# IOTBee-v1_1.net
KiCad netlist of a schematic drawn in EAGLE
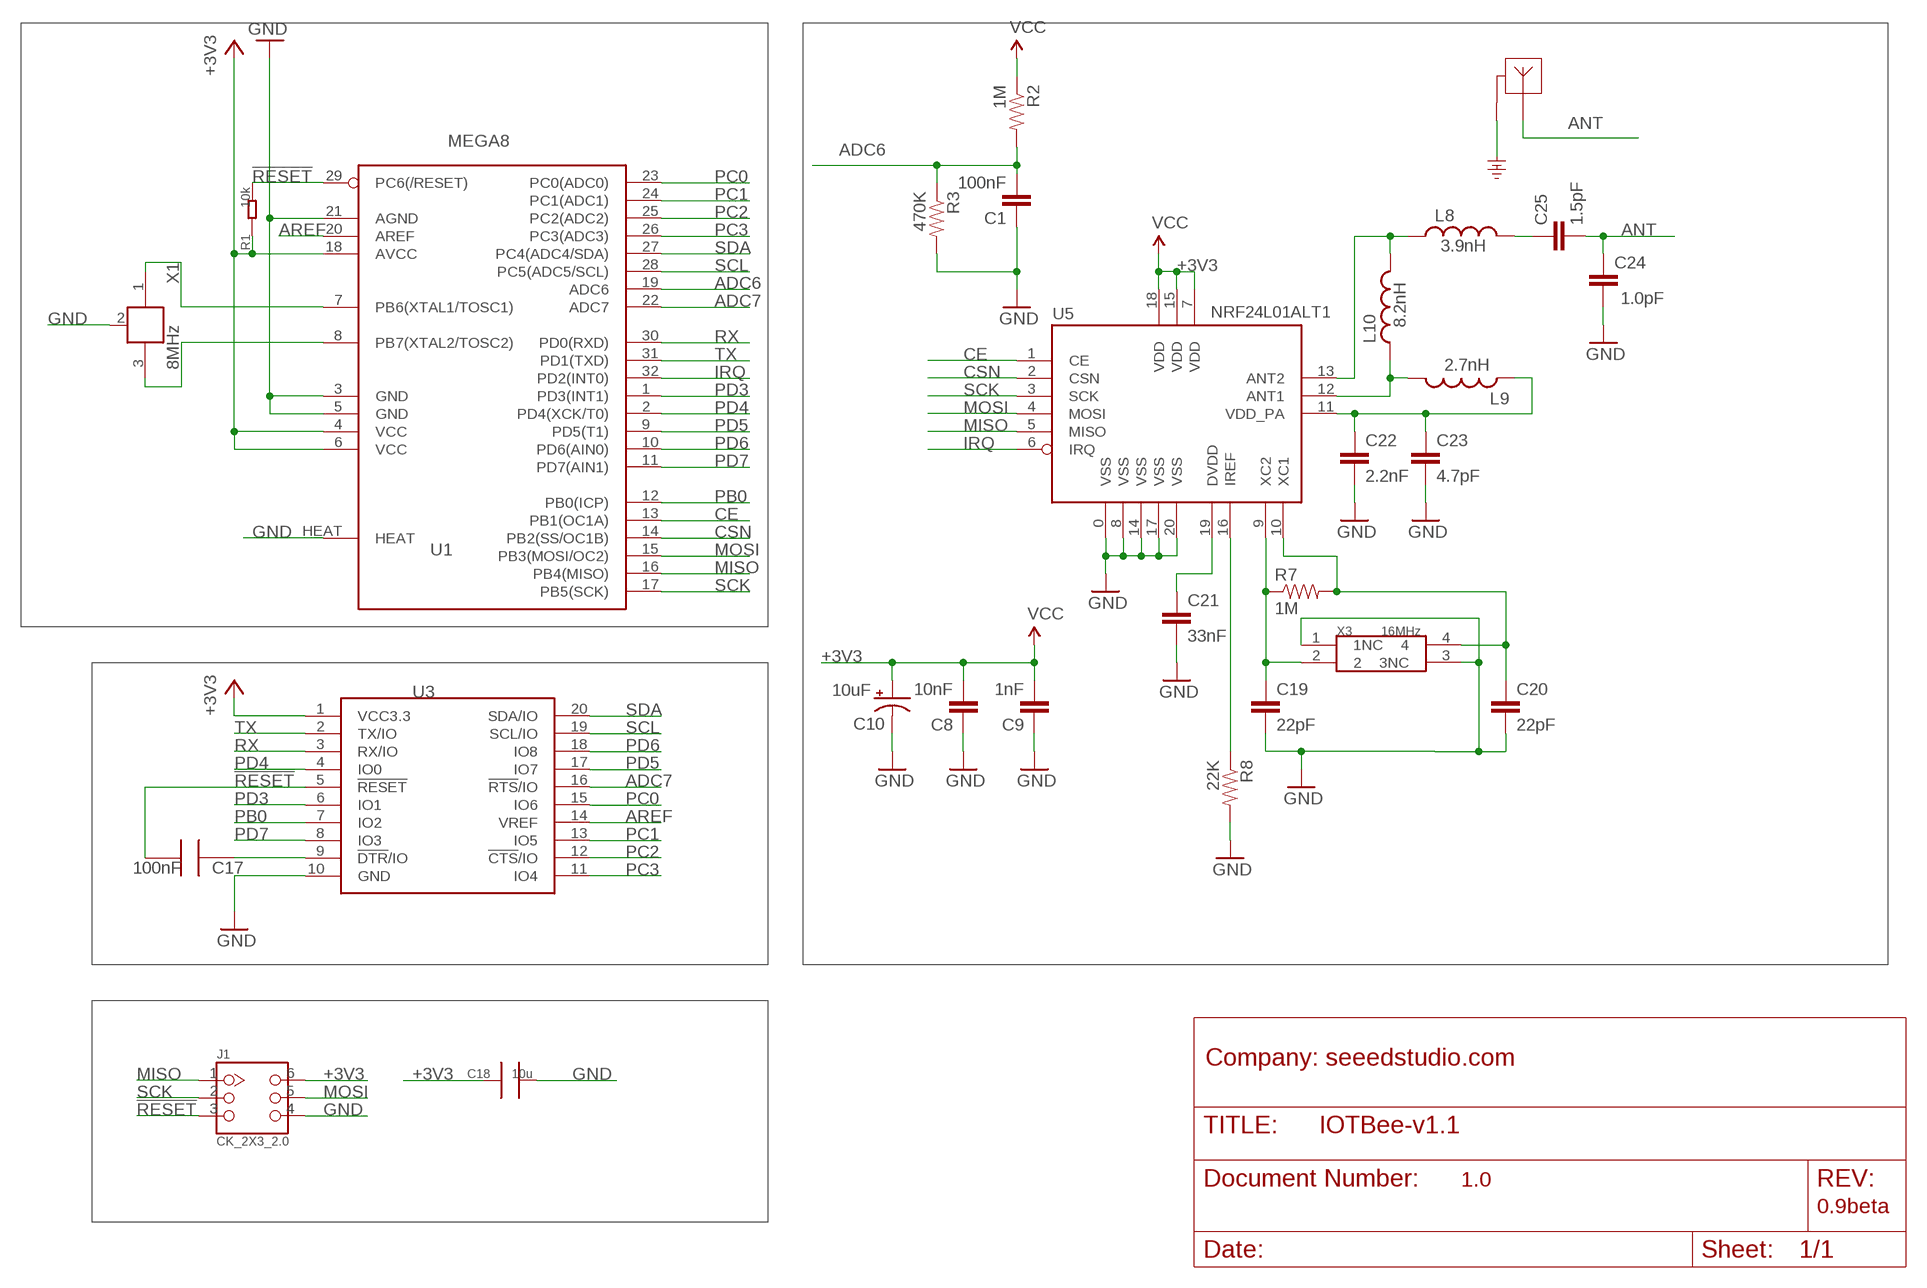
[diagram p0: schematic, sheet 1]

(export (version "E")
  (design (tool "Eeschema 10.0.6"))
  (components
    (comp (ref "ANT1")
      (value "2.4G-ANT")
      (footprint "eagle-import:2.4G-ANT")
      (libsource (lib "eagle-import") (part "2.4G-ANT"))
    )
    (comp (ref "C1")
      (value "100nF")
      (footprint "eagle-import:0402-CAP")
      (libsource (lib "eagle-import") (part "CAP0402-CAP"))
    )
    (comp (ref "C8")
      (value "10nF")
      (footprint "eagle-import:0402-CAP")
      (libsource (lib "eagle-import") (part "CAP0402-CAP"))
    )
    (comp (ref "C9")
      (value "1nF")
      (footprint "eagle-import:0402-CAP")
      (libsource (lib "eagle-import") (part "CAP0402-CAP"))
    )
    (comp (ref "C10")
      (value "10uF")
      (footprint "eagle-import:EIA3528")
      (libsource (lib "eagle-import") (part "CAP_POL3528"))
    )
    (comp (ref "C17")
      (value "100nF")
      (footprint "eagle-import:0603_S")
      (libsource (lib "eagle-import") (part "C0603_S"))
    )
    (comp (ref "C18")
      (value "10u")
      (footprint "eagle-import:0805")
      (libsource (lib "eagle-import") (part "C0805"))
    )
    (comp (ref "C19")
      (value "22pF")
      (footprint "eagle-import:0402-CAP")
      (libsource (lib "eagle-import") (part "CAP0402-CAP"))
    )
    (comp (ref "C20")
      (value "22pF")
      (footprint "eagle-import:0402-CAP")
      (libsource (lib "eagle-import") (part "CAP0402-CAP"))
    )
    (comp (ref "C21")
      (value "33nF")
      (footprint "eagle-import:0402-CAP")
      (libsource (lib "eagle-import") (part "CAP0402-CAP"))
    )
    (comp (ref "C22")
      (value "2.2nF")
      (footprint "eagle-import:0402-CAP")
      (libsource (lib "eagle-import") (part "CAP0402-CAP"))
    )
    (comp (ref "C23")
      (value "4.7pF")
      (footprint "eagle-import:0402-CAP")
      (libsource (lib "eagle-import") (part "CAP0402-CAP"))
    )
    (comp (ref "C24")
      (value "1.0pF")
      (footprint "eagle-import:0402-CAP")
      (libsource (lib "eagle-import") (part "CAP0402-CAP"))
    )
    (comp (ref "C25")
      (value "1.5pF")
      (footprint "eagle-import:0402-CAP")
      (libsource (lib "eagle-import") (part "CAP0402-CAP"))
    )
    (comp (ref "J1")
      (value "CK_2X3_2.0")
      (footprint "eagle-import:CK_2X3_2.0")
      (libsource (lib "eagle-import") (part "CK_2X3_2.0"))
    )
    (comp (ref "L8")
      (value "3.9nH")
      (footprint "eagle-import:C0402")
      (libsource (lib "eagle-import") (part "INDUCTOR0402"))
    )
    (comp (ref "L9")
      (value "2.7nH")
      (footprint "eagle-import:C0402")
      (libsource (lib "eagle-import") (part "INDUCTOR0402"))
    )
    (comp (ref "L10")
      (value "8.2nH")
      (footprint "eagle-import:C0402")
      (libsource (lib "eagle-import") (part "INDUCTOR0402"))
    )
    (comp (ref "R1")
      (value "10k")
      (footprint "eagle-import:0603_S")
      (libsource (lib "eagle-import") (part "R0603_S"))
    )
    (comp (ref "R2")
      (value "1M")
      (footprint "eagle-import:0402-RES")
      (libsource (lib "eagle-import") (part "RESISTOR0402-RES"))
    )
    (comp (ref "R3")
      (value "470K")
      (footprint "eagle-import:0402-RES")
      (libsource (lib "eagle-import") (part "RESISTOR0402-RES"))
    )
    (comp (ref "R7")
      (value "1M")
      (footprint "eagle-import:0402-RES")
      (libsource (lib "eagle-import") (part "RESISTOR0402-RES"))
    )
    (comp (ref "R8")
      (value "22K")
      (footprint "eagle-import:0402-RES")
      (libsource (lib "eagle-import") (part "RESISTOR0402-RES"))
    )
    (comp (ref "U1")
      (value "MEGA8")
      (footprint "eagle-import:MLF32X")
      (libsource (lib "eagle-import") (part "MEGA8"))
    )
    (comp (ref "U3")
      (value "BEE-OPENBEE-BTSMD")
      (footprint "eagle-import:20P-SMD-2.0-BT")
      (libsource (lib "eagle-import") (part "BEE-OPENBEE-BTSMD"))
    )
    (comp (ref "U5")
      (value "NRF24L01ALT1")
      (footprint "eagle-import:QFN20_ALT1")
      (libsource (lib "eagle-import") (part "NRF24L01ALT1"))
    )
    (comp (ref "X1")
      (value "8MHz")
      (footprint "eagle-import:XTAL_3X2")
      (libsource (lib "eagle-import") (part "XTAL_NCVER"))
    )
    (comp (ref "X3")
      (value "16MHz")
      (footprint "eagle-import:X3225")
      (libsource (lib "eagle-import") (part "XTAL_SMD_3225"))
    )
  )
  (nets
    (net (code "1") (name "+3V3") (class "Default")
      (node (ref "C10") (pin "A") (pinfunction "+_A") (pintype "passive"))
      (node (ref "C18") (pin "1") (pinfunction "1_1") (pintype "bidirectional"))
      (node (ref "C8") (pin "2") (pinfunction "2_2") (pintype "passive"))
      (node (ref "C9") (pin "2") (pinfunction "2_2") (pintype "passive"))
      (node (ref "J1") (pin "6") (pinfunction "P$6_6") (pintype "bidirectional"))
      (node (ref "R1") (pin "1") (pinfunction "1_1") (pintype "bidirectional"))
      (node (ref "R2") (pin "1") (pinfunction "1_1") (pintype "passive"))
      (node (ref "U1") (pin "18") (pinfunction "AVCC_18") (pintype "bidirectional"))
      (node (ref "U1") (pin "4") (pinfunction "VCC_4") (pintype "bidirectional"))
      (node (ref "U1") (pin "6") (pinfunction "VCC_6") (pintype "bidirectional"))
      (node (ref "U3") (pin "1") (pinfunction "VCC3.3_1") (pintype "bidirectional"))
      (node (ref "U5") (pin "15") (pinfunction "VDD_15") (pintype "power_in"))
      (node (ref "U5") (pin "18") (pinfunction "VDD_18") (pintype "power_in"))
      (node (ref "U5") (pin "7") (pinfunction "VDD_7") (pintype "power_in"))
    )
    (net (code "2") (name "/ADC6") (class "Default")
      (node (ref "C1") (pin "2") (pinfunction "2_2") (pintype "passive"))
      (node (ref "R2") (pin "2") (pinfunction "2_2") (pintype "passive"))
      (node (ref "R3") (pin "1") (pinfunction "1_1") (pintype "passive"))
      (node (ref "U1") (pin "19") (pinfunction "ADC6_19") (pintype "bidirectional"))
    )
    (net (code "3") (name "/ADC7") (class "Default")
      (node (ref "U1") (pin "22") (pinfunction "ADC7_22") (pintype "bidirectional"))
      (node (ref "U3") (pin "16") (pinfunction "~{RTS}/IO_16") (pintype "bidirectional"))
    )
    (net (code "4") (name "/ANT") (class "Default")
      (node (ref "ANT1") (pin "2") (pinfunction "2_2") (pintype "bidirectional"))
      (node (ref "C24") (pin "2") (pinfunction "2_2") (pintype "passive"))
      (node (ref "C25") (pin "2") (pinfunction "2_2") (pintype "passive"))
    )
    (net (code "5") (name "/AREF") (class "Default")
      (node (ref "U1") (pin "20") (pinfunction "AREF_20") (pintype "bidirectional"))
      (node (ref "U3") (pin "14") (pinfunction "VREF_14") (pintype "bidirectional"))
    )
    (net (code "6") (name "/CE") (class "Default")
      (node (ref "U1") (pin "13") (pinfunction "PB1(OC1A)_13") (pintype "bidirectional"))
      (node (ref "U5") (pin "1") (pinfunction "CE_1") (pintype "input"))
    )
    (net (code "7") (name "/CSN") (class "Default")
      (node (ref "U1") (pin "14") (pinfunction "PB2(SS/OC1B)_14") (pintype "bidirectional"))
      (node (ref "U5") (pin "2") (pinfunction "CSN_2") (pintype "input"))
    )
    (net (code "8") (name "/IRQ") (class "Default")
      (node (ref "U1") (pin "32") (pinfunction "PD2(INT0)_32") (pintype "bidirectional"))
      (node (ref "U5") (pin "6") (pinfunction "IRQ_6") (pintype "output"))
    )
    (net (code "9") (name "/MISO") (class "Default")
      (node (ref "J1") (pin "1") (pinfunction "P$1_1") (pintype "bidirectional"))
      (node (ref "U1") (pin "16") (pinfunction "PB4(MISO)_16") (pintype "bidirectional"))
      (node (ref "U5") (pin "5") (pinfunction "MISO_5") (pintype "output"))
    )
    (net (code "10") (name "/MOSI") (class "Default")
      (node (ref "J1") (pin "5") (pinfunction "P$5_5") (pintype "bidirectional"))
      (node (ref "U1") (pin "15") (pinfunction "PB3(MOSI/OC2)_15") (pintype "bidirectional"))
      (node (ref "U5") (pin "4") (pinfunction "MOSI_4") (pintype "input"))
    )
    (net (code "11") (name "/PB0") (class "Default")
      (node (ref "U1") (pin "12") (pinfunction "PB0(ICP)_12") (pintype "bidirectional"))
      (node (ref "U3") (pin "7") (pinfunction "IO2_7") (pintype "bidirectional"))
    )
    (net (code "12") (name "/PC0") (class "Default")
      (node (ref "U1") (pin "23") (pinfunction "PC0(ADC0)_23") (pintype "bidirectional"))
      (node (ref "U3") (pin "15") (pinfunction "IO6_15") (pintype "bidirectional"))
    )
    (net (code "13") (name "/PC1") (class "Default")
      (node (ref "U1") (pin "24") (pinfunction "PC1(ADC1)_24") (pintype "bidirectional"))
      (node (ref "U3") (pin "13") (pinfunction "IO5_13") (pintype "bidirectional"))
    )
    (net (code "14") (name "/PC2") (class "Default")
      (node (ref "U1") (pin "25") (pinfunction "PC2(ADC2)_25") (pintype "bidirectional"))
      (node (ref "U3") (pin "12") (pinfunction "~{CTS}/IO_12") (pintype "bidirectional"))
    )
    (net (code "15") (name "/PC3") (class "Default")
      (node (ref "U1") (pin "26") (pinfunction "PC3(ADC3)_26") (pintype "bidirectional"))
      (node (ref "U3") (pin "11") (pinfunction "IO4_11") (pintype "bidirectional"))
    )
    (net (code "16") (name "/PD3") (class "Default")
      (node (ref "U1") (pin "1") (pinfunction "PD3(INT1)_1") (pintype "bidirectional"))
      (node (ref "U3") (pin "6") (pinfunction "IO1_6") (pintype "bidirectional"))
    )
    (net (code "17") (name "/PD4") (class "Default")
      (node (ref "U1") (pin "2") (pinfunction "PD4(XCK/T0)_2") (pintype "bidirectional"))
      (node (ref "U3") (pin "4") (pinfunction "IO0_4") (pintype "bidirectional"))
    )
    (net (code "18") (name "/PD5") (class "Default")
      (node (ref "U1") (pin "9") (pinfunction "PD5(T1)_9") (pintype "bidirectional"))
      (node (ref "U3") (pin "17") (pinfunction "IO7_17") (pintype "bidirectional"))
    )
    (net (code "19") (name "/PD6") (class "Default")
      (node (ref "U1") (pin "10") (pinfunction "PD6(AIN0)_10") (pintype "bidirectional"))
      (node (ref "U3") (pin "18") (pinfunction "IO8_18") (pintype "bidirectional"))
    )
    (net (code "20") (name "/PD7") (class "Default")
      (node (ref "U1") (pin "11") (pinfunction "PD7(AIN1)_11") (pintype "bidirectional"))
      (node (ref "U3") (pin "8") (pinfunction "IO3_8") (pintype "bidirectional"))
    )
    (net (code "21") (name "/RX") (class "Default")
      (node (ref "U1") (pin "30") (pinfunction "PD0(RXD)_30") (pintype "bidirectional"))
      (node (ref "U3") (pin "3") (pinfunction "RX/IO_3") (pintype "bidirectional"))
    )
    (net (code "22") (name "/SCK") (class "Default")
      (node (ref "J1") (pin "2") (pinfunction "P$2_2") (pintype "bidirectional"))
      (node (ref "U1") (pin "17") (pinfunction "PB5(SCK)_17") (pintype "bidirectional"))
      (node (ref "U5") (pin "3") (pinfunction "SCK_3") (pintype "input"))
    )
    (net (code "23") (name "/SCL") (class "Default")
      (node (ref "U1") (pin "28") (pinfunction "PC5(ADC5/SCL)_28") (pintype "bidirectional"))
      (node (ref "U3") (pin "19") (pinfunction "SCL/IO_19") (pintype "bidirectional"))
    )
    (net (code "24") (name "/SDA") (class "Default")
      (node (ref "U1") (pin "27") (pinfunction "PC4(ADC4/SDA)_27") (pintype "bidirectional"))
      (node (ref "U3") (pin "20") (pinfunction "SDA/IO_20") (pintype "bidirectional"))
    )
    (net (code "25") (name "/TX") (class "Default")
      (node (ref "U1") (pin "31") (pinfunction "PD1(TXD)_31") (pintype "bidirectional"))
      (node (ref "U3") (pin "2") (pinfunction "TX/IO_2") (pintype "bidirectional"))
    )
    (net (code "26") (name "/~{RESET}") (class "Default")
      (node (ref "C17") (pin "2") (pinfunction "2_2") (pintype "bidirectional"))
      (node (ref "J1") (pin "3") (pinfunction "P$3_3") (pintype "bidirectional"))
      (node (ref "R1") (pin "2") (pinfunction "2_2") (pintype "bidirectional"))
      (node (ref "U1") (pin "29") (pinfunction "PC6(/RESET)_29") (pintype "bidirectional"))
      (node (ref "U3") (pin "5") (pinfunction "~{RESET}_5") (pintype "bidirectional"))
    )
    (net (code "27") (name "GND") (class "Default")
      (node (ref "ANT1") (pin "1") (pinfunction "1_1") (pintype "bidirectional"))
      (node (ref "C1") (pin "1") (pinfunction "1_1") (pintype "passive"))
      (node (ref "C10") (pin "C") (pinfunction "-_C") (pintype "passive"))
      (node (ref "C18") (pin "2") (pinfunction "2_2") (pintype "bidirectional"))
      (node (ref "C19") (pin "2") (pinfunction "2_2") (pintype "passive"))
      (node (ref "C20") (pin "2") (pinfunction "2_2") (pintype "passive"))
      (node (ref "C21") (pin "2") (pinfunction "2_2") (pintype "passive"))
      (node (ref "C22") (pin "2") (pinfunction "2_2") (pintype "passive"))
      (node (ref "C23") (pin "2") (pinfunction "2_2") (pintype "passive"))
      (node (ref "C24") (pin "1") (pinfunction "1_1") (pintype "passive"))
      (node (ref "C8") (pin "1") (pinfunction "1_1") (pintype "passive"))
      (node (ref "C9") (pin "1") (pinfunction "1_1") (pintype "passive"))
      (node (ref "J1") (pin "4") (pinfunction "P$4_4") (pintype "bidirectional"))
      (node (ref "R3") (pin "2") (pinfunction "2_2") (pintype "passive"))
      (node (ref "R8") (pin "2") (pinfunction "2_2") (pintype "passive"))
      (node (ref "U1") (pin "21") (pinfunction "AGND_21") (pintype "bidirectional"))
      (node (ref "U1") (pin "3") (pinfunction "GND_3") (pintype "bidirectional"))
      (node (ref "U1") (pin "5") (pinfunction "GND_5") (pintype "bidirectional"))
      (node (ref "U1") (pin "HEAT") (pinfunction "HEAT_HEAT") (pintype "bidirectional"))
      (node (ref "U3") (pin "10") (pinfunction "GND_10") (pintype "bidirectional"))
      (node (ref "U5") (pin "0") (pinfunction "VSS_0") (pintype "power_in"))
      (node (ref "U5") (pin "14") (pinfunction "VSS_14") (pintype "power_in"))
      (node (ref "U5") (pin "17") (pinfunction "VSS_17") (pintype "power_in"))
      (node (ref "U5") (pin "20") (pinfunction "VSS_20") (pintype "power_in"))
      (node (ref "U5") (pin "8") (pinfunction "VSS_8") (pintype "power_in"))
      (node (ref "X1") (pin "2") (pinfunction "GND_2") (pintype "bidirectional"))
      (node (ref "X3") (pin "1") (pinfunction "1NC_1") (pintype "bidirectional"))
      (node (ref "X3") (pin "3") (pinfunction "3NC_3") (pintype "bidirectional"))
    )
    (net (code "28") (name "Net-(C25-Pad1)") (class "Default")
      (node (ref "C25") (pin "1") (pinfunction "1_1") (pintype "passive"))
      (node (ref "L8") (pin "2") (pinfunction "2_2") (pintype "passive"))
    )
    (net (code "29") (name "Net-(U1-PB6(XTAL1{slash}TOSC1))") (class "Default")
      (node (ref "U1") (pin "7") (pinfunction "PB6(XTAL1/TOSC1)_7") (pintype "bidirectional"))
      (node (ref "X1") (pin "1") (pinfunction "1_1") (pintype "bidirectional"))
    )
    (net (code "30") (name "Net-(U1-PB7(XTAL2{slash}TOSC2))") (class "Default")
      (node (ref "U1") (pin "8") (pinfunction "PB7(XTAL2/TOSC2)_8") (pintype "bidirectional"))
      (node (ref "X1") (pin "3") (pinfunction "2_3") (pintype "bidirectional"))
    )
    (net (code "31") (name "Net-(U3-~{DTR}{slash}IO)") (class "Default")
      (node (ref "C17") (pin "1") (pinfunction "1_1") (pintype "bidirectional"))
      (node (ref "U3") (pin "9") (pinfunction "~{DTR}/IO_9") (pintype "bidirectional"))
    )
    (net (code "32") (name "Net-(U5-ANT1)") (class "Default")
      (node (ref "L10") (pin "1") (pinfunction "1_1") (pintype "passive"))
      (node (ref "L9") (pin "2") (pinfunction "2_2") (pintype "passive"))
      (node (ref "U5") (pin "12") (pinfunction "ANT1_12") (pintype "output"))
    )
    (net (code "33") (name "Net-(U5-ANT2)") (class "Default")
      (node (ref "L10") (pin "2") (pinfunction "2_2") (pintype "passive"))
      (node (ref "L8") (pin "1") (pinfunction "1_1") (pintype "passive"))
      (node (ref "U5") (pin "13") (pinfunction "ANT2_13") (pintype "output"))
    )
    (net (code "34") (name "Net-(U5-DVDD)") (class "Default")
      (node (ref "C21") (pin "1") (pinfunction "1_1") (pintype "passive"))
      (node (ref "U5") (pin "19") (pinfunction "DVDD_19") (pintype "power_in"))
    )
    (net (code "35") (name "Net-(U5-IREF)") (class "Default")
      (node (ref "R8") (pin "1") (pinfunction "1_1") (pintype "passive"))
      (node (ref "U5") (pin "16") (pinfunction "IREF_16") (pintype "input"))
    )
    (net (code "36") (name "Net-(U5-VDD_PA)") (class "Default")
      (node (ref "C22") (pin "1") (pinfunction "1_1") (pintype "passive"))
      (node (ref "C23") (pin "1") (pinfunction "1_1") (pintype "passive"))
      (node (ref "L9") (pin "1") (pinfunction "1_1") (pintype "passive"))
      (node (ref "U5") (pin "11") (pinfunction "VDD_PA_11") (pintype "power_in"))
    )
    (net (code "37") (name "Net-(U5-XC1)") (class "Default")
      (node (ref "C20") (pin "1") (pinfunction "1_1") (pintype "passive"))
      (node (ref "R7") (pin "2") (pinfunction "2_2") (pintype "passive"))
      (node (ref "U5") (pin "10") (pinfunction "XC1_10") (pintype "input"))
      (node (ref "X3") (pin "4") (pinfunction "4_4") (pintype "bidirectional"))
    )
    (net (code "38") (name "Net-(U5-XC2)") (class "Default")
      (node (ref "C19") (pin "1") (pinfunction "1_1") (pintype "passive"))
      (node (ref "R7") (pin "1") (pinfunction "1_1") (pintype "passive"))
      (node (ref "U5") (pin "9") (pinfunction "XC2_9") (pintype "input"))
      (node (ref "X3") (pin "2") (pinfunction "2_2") (pintype "bidirectional"))
    )
  )
)
